# Sensors.net
KiCad netlist of a schematic drawn in Altium Designer
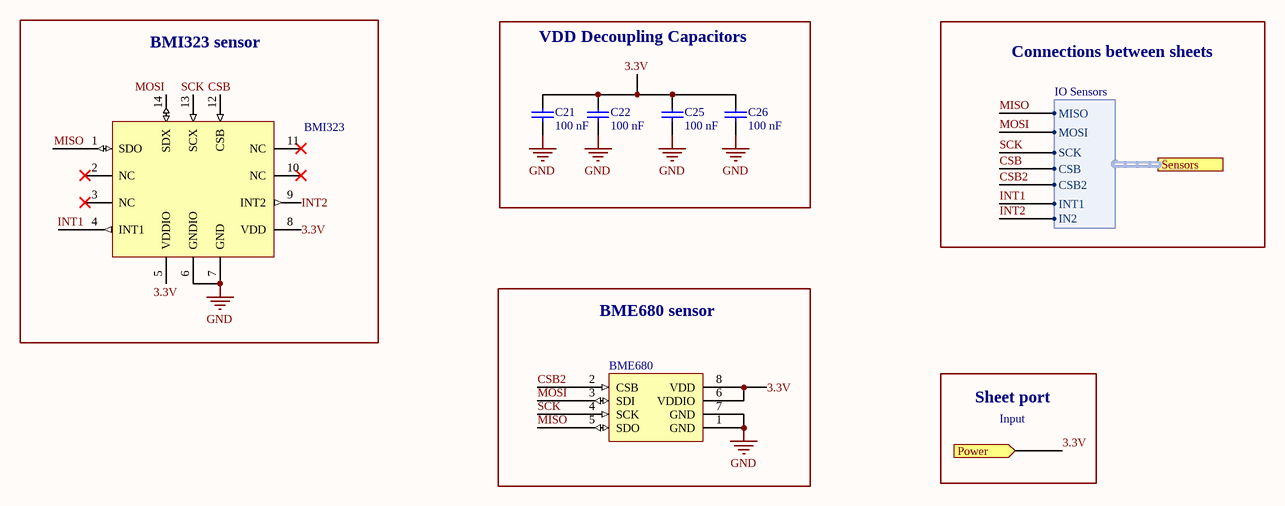
[diagram p0: Sensors.SchDoc]

(export (version "E")
  (design (tool "Eeschema 10.0.6"))
  (components
    (comp (ref "BME")
      (value "BME680_Sen_4in1")
      (footprint "BME_LGA8")
      (libsource (lib "FEEL2324") (part "BME680_Sen_4in1"))
    )
    (comp (ref "BMI") (value "BMI323") (footprint "BMI323") (libsource (lib "FEEL2324") (part "BMI323")))
    (comp (ref "C21")
      (value "100 nF")
      (footprint "CAPC1005X55X30LL05T10")
      (fields (field (name "MANUFACTURER") "Kemet") (field (name "PART NUMBER") "C0402C104K4RACTU"))
      (libsource (lib "Altium Content Vault") (part "CAP"))
    )
    (comp (ref "C22")
      (value "100 nF")
      (footprint "CAPC1005X55X30LL05T10")
      (fields (field (name "MANUFACTURER") "Kemet") (field (name "PART NUMBER") "C0402C104K4RACTU"))
      (libsource (lib "Altium Content Vault") (part "CAP"))
    )
    (comp (ref "C25")
      (value "100 nF")
      (footprint "CAPC1005X55X30LL05T10")
      (fields (field (name "MANUFACTURER") "Kemet") (field (name "PART NUMBER") "C0402C104K4RACTU"))
      (libsource (lib "Altium Content Vault") (part "CAP"))
    )
    (comp (ref "C26")
      (value "100 nF")
      (footprint "CAPC1005X55X30LL05T10")
      (fields (field (name "MANUFACTURER") "Kemet") (field (name "PART NUMBER") "C0402C104K4RACTU"))
      (libsource (lib "Altium Content Vault") (part "CAP"))
    )
  )
  (nets
    (net (code "3") (name "/3.3V") (class "Default")
      (node (ref "BME") (pin "6") (pinfunction "VDDIO_6") (pintype "passive"))
      (node (ref "BME") (pin "8") (pinfunction "VDD_8") (pintype "passive"))
      (node (ref "BMI") (pin "5") (pinfunction "VDDIO_5") (pintype "passive"))
      (node (ref "BMI") (pin "8") (pinfunction "VDD_8") (pintype "passive"))
      (node (ref "C21") (pin "2") (pinfunction "2_2") (pintype "passive"))
      (node (ref "C22") (pin "2") (pinfunction "2_2") (pintype "passive"))
      (node (ref "C25") (pin "2") (pinfunction "2_2") (pintype "passive"))
      (node (ref "C26") (pin "2") (pinfunction "2_2") (pintype "passive"))
    )
    (net (code "4") (name "/CSB") (class "Default")
      (node (ref "BMI") (pin "12") (pinfunction "CSB_12") (pintype "input"))
    )
    (net (code "5") (name "/CSB2") (class "Default")
      (node (ref "BME") (pin "2") (pinfunction "CSB_2") (pintype "input"))
    )
    (net (code "6") (name "/INT1") (class "Default")
      (node (ref "BMI") (pin "4") (pinfunction "INT1_4") (pintype "output"))
    )
    (net (code "7") (name "/INT2") (class "Default")
      (node (ref "BMI") (pin "9") (pinfunction "INT2_9") (pintype "output"))
    )
    (net (code "8") (name "/MISO") (class "Default")
      (node (ref "BME") (pin "5") (pinfunction "SDO_5") (pintype "bidirectional"))
      (node (ref "BMI") (pin "1") (pinfunction "SDO_1") (pintype "bidirectional"))
    )
    (net (code "9") (name "/MOSI") (class "Default")
      (node (ref "BME") (pin "3") (pinfunction "SDI_3") (pintype "bidirectional"))
      (node (ref "BMI") (pin "14") (pinfunction "SDX_14") (pintype "bidirectional"))
    )
    (net (code "10") (name "/SCK") (class "Default")
      (node (ref "BME") (pin "4") (pinfunction "SCK_4") (pintype "input"))
      (node (ref "BMI") (pin "13") (pinfunction "SCX_13") (pintype "input"))
    )
    (net (code "12") (name "GND") (class "Default")
      (node (ref "BME") (pin "1") (pinfunction "GND_1") (pintype "power_in"))
      (node (ref "BME") (pin "7") (pinfunction "GND_7") (pintype "power_in"))
      (node (ref "BMI") (pin "6") (pinfunction "GNDIO_6") (pintype "power_in"))
      (node (ref "BMI") (pin "7") (pinfunction "GND_7") (pintype "power_in"))
      (node (ref "C21") (pin "1") (pinfunction "1_1") (pintype "passive"))
      (node (ref "C22") (pin "1") (pinfunction "1_1") (pintype "passive"))
      (node (ref "C25") (pin "1") (pinfunction "1_1") (pintype "passive"))
      (node (ref "C26") (pin "1") (pinfunction "1_1") (pintype "passive"))
    )
    (net (code "13") (name "unconnected-(BMI-NC-Pad2)") (class "Default")
      (node (ref "BMI") (pin "2") (pinfunction "NC_2") (pintype "passive+no_connect"))
    )
    (net (code "14") (name "unconnected-(BMI-NC-Pad3)") (class "Default")
      (node (ref "BMI") (pin "3") (pinfunction "NC_3") (pintype "passive+no_connect"))
    )
    (net (code "15") (name "unconnected-(BMI-NC-Pad10)") (class "Default")
      (node (ref "BMI") (pin "10") (pinfunction "NC_10") (pintype "passive+no_connect"))
    )
    (net (code "16") (name "unconnected-(BMI-NC-Pad11)") (class "Default")
      (node (ref "BMI") (pin "11") (pinfunction "NC_11") (pintype "passive+no_connect"))
    )
  )
)
